# ATMega16Motherboard1.net
KiCad netlist of a schematic drawn in EAGLE
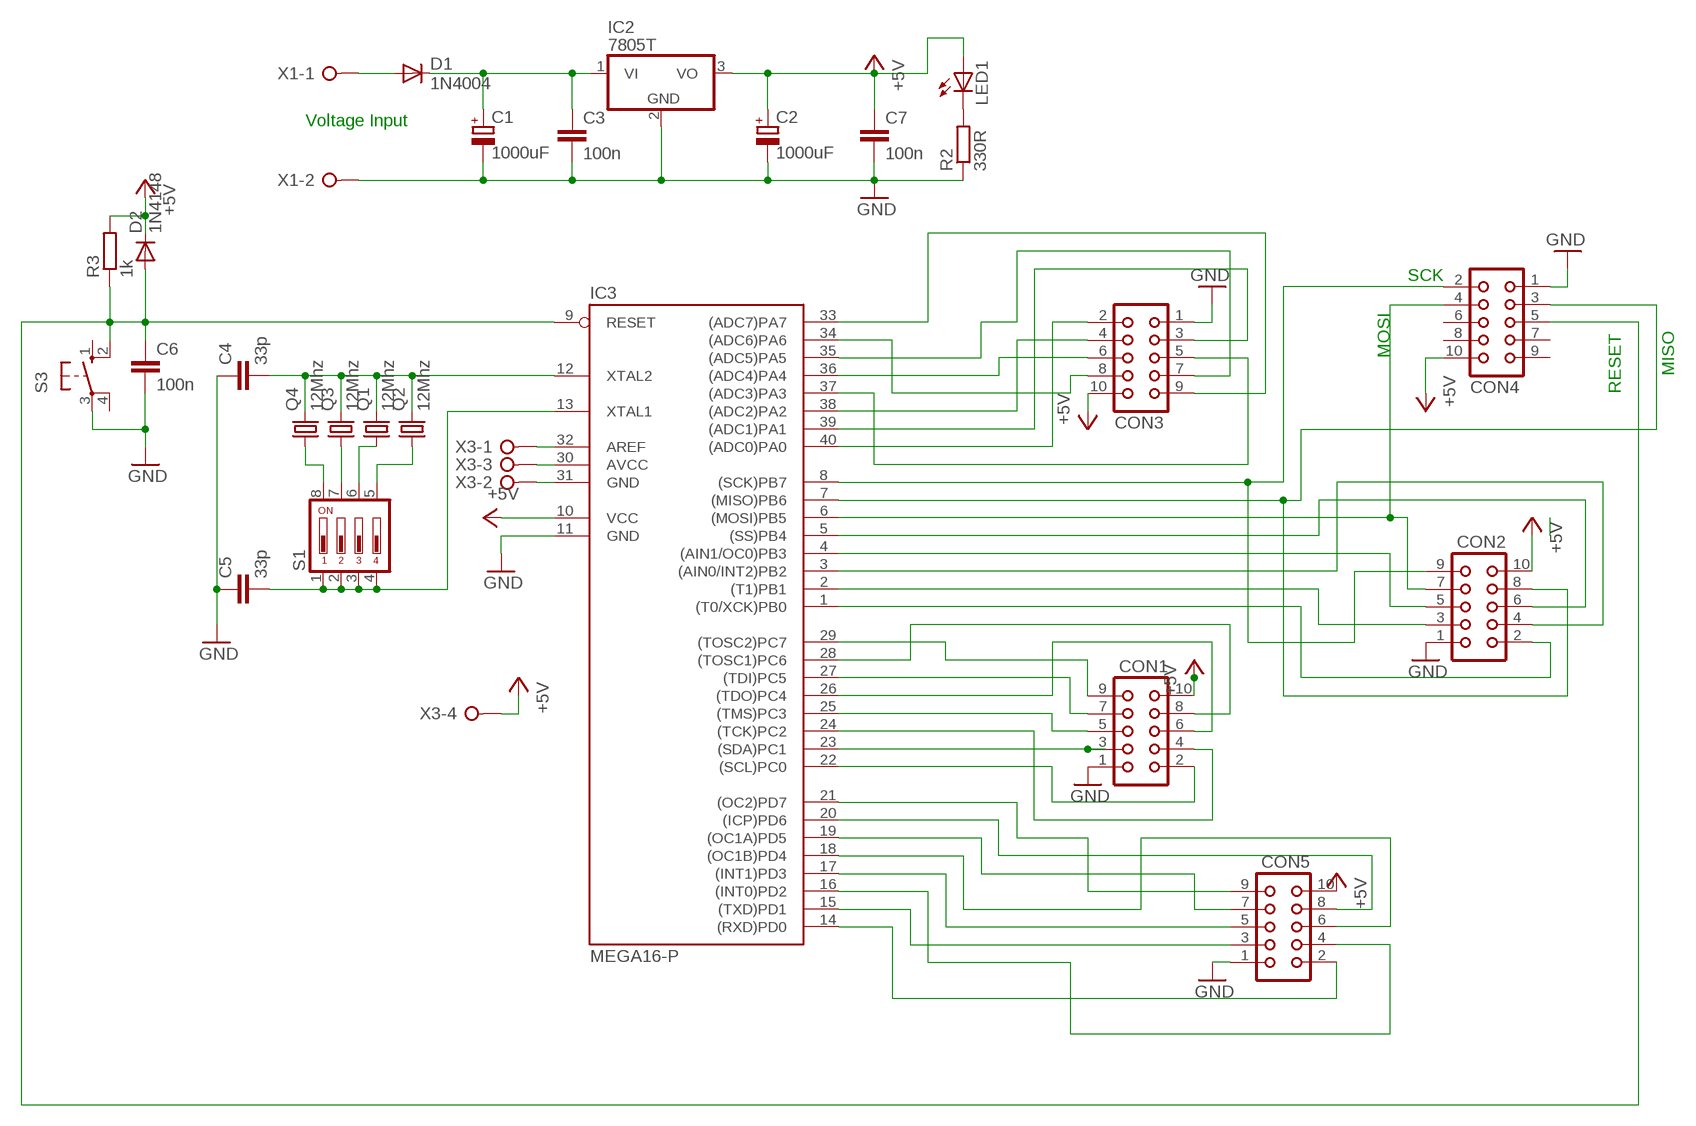
[diagram p0: schematic, sheet 1]

(export (version "E")
  (design (tool "Eeschema 10.0.6"))
  (components
    (comp (ref "C1")
      (value "1000uF")
      (footprint "eagle-import:E2,5-7")
      (libsource (lib "eagle-import") (part "CPOL-EUE2.5-7"))
    )
    (comp (ref "C2")
      (value "1000uF")
      (footprint "eagle-import:E2,5-7")
      (libsource (lib "eagle-import") (part "CPOL-EUE2.5-7"))
    )
    (comp (ref "C3")
      (value "100n")
      (footprint "eagle-import:C025-024X044")
      (libsource (lib "eagle-import") (part "C-EU025-024X044"))
    )
    (comp (ref "C4")
      (value "33p")
      (footprint "eagle-import:C025-024X044")
      (libsource (lib "eagle-import") (part "C-EU025-024X044"))
    )
    (comp (ref "C5")
      (value "33p")
      (footprint "eagle-import:C025-024X044")
      (libsource (lib "eagle-import") (part "C-EU025-024X044"))
    )
    (comp (ref "C6")
      (value "100n")
      (footprint "eagle-import:C025-024X044")
      (libsource (lib "eagle-import") (part "C-EU025-024X044"))
    )
    (comp (ref "C7")
      (value "100n")
      (footprint "eagle-import:C025-024X044")
      (libsource (lib "eagle-import") (part "C-EU025-024X044"))
    )
    (comp (ref "CON1")
      (value "CON10")
      (footprint "eagle-import:CON10")
      (libsource (lib "eagle-import") (part "CON10"))
    )
    (comp (ref "CON2")
      (value "CON10")
      (footprint "eagle-import:CON10")
      (libsource (lib "eagle-import") (part "CON10"))
    )
    (comp (ref "CON3")
      (value "CON10")
      (footprint "eagle-import:CON10")
      (libsource (lib "eagle-import") (part "CON10"))
    )
    (comp (ref "CON4")
      (value "CON10")
      (footprint "eagle-import:CON10")
      (libsource (lib "eagle-import") (part "CON10"))
    )
    (comp (ref "CON5")
      (value "CON10")
      (footprint "eagle-import:CON10")
      (libsource (lib "eagle-import") (part "CON10"))
    )
    (comp (ref "D1")
      (value "1N4004")
      (footprint "eagle-import:DO41-10")
      (libsource (lib "eagle-import") (part "1N4004"))
    )
    (comp (ref "D2")
      (value "1N4148")
      (footprint "eagle-import:DO35-10")
      (libsource (lib "eagle-import") (part "1N4148"))
    )
    (comp (ref "IC2")
      (value "7805T")
      (footprint "eagle-import:TO220H")
      (libsource (lib "eagle-import") (part "78T05"))
    )
    (comp (ref "IC3")
      (value "MEGA16-P")
      (footprint "eagle-import:DIL40")
      (fields (field (name "MPN") "ATMEGA16-16PU"))
      (libsource (lib "eagle-import") (part "MEGA16-P"))
    )
    (comp (ref "LED1")
      (value "LED5MM")
      (footprint "eagle-import:LED5MM")
      (libsource (lib "eagle-import") (part "LED5MM"))
    )
    (comp (ref "Q1")
      (value "12Mhz")
      (footprint "eagle-import:HC18U-V")
      (libsource (lib "eagle-import") (part "CRYSTALHC18U-V"))
    )
    (comp (ref "Q2")
      (value "12Mhz")
      (footprint "eagle-import:HC18U-V")
      (libsource (lib "eagle-import") (part "CRYSTALHC18U-V"))
    )
    (comp (ref "Q3")
      (value "12Mhz")
      (footprint "eagle-import:HC18U-V")
      (libsource (lib "eagle-import") (part "CRYSTALHC18U-V"))
    )
    (comp (ref "Q4")
      (value "12Mhz")
      (footprint "eagle-import:HC18U-V")
      (libsource (lib "eagle-import") (part "CRYSTALHC18U-V"))
    )
    (comp (ref "R2")
      (value "330R")
      (footprint "eagle-import:0204_5")
      (libsource (lib "eagle-import") (part "R-EU_0204/5"))
    )
    (comp (ref "R3")
      (value "1k")
      (footprint "eagle-import:0204_5")
      (libsource (lib "eagle-import") (part "R-EU_0204/5"))
    )
    (comp (ref "S1")
      (value "DIP04YL")
      (footprint "eagle-import:DIP04YL")
      (libsource (lib "eagle-import") (part "DIP04YL"))
    )
    (comp (ref "S3")
      (value "10-XX")
      (footprint "eagle-import:B3F-10XX")
      (fields (field (name "MPN") "B3F-1000"))
      (libsource (lib "eagle-import") (part "10-XX"))
    )
    (comp (ref "X1")
      (value "W237-02P")
      (footprint "eagle-import:W237-132")
      (libsource (lib "eagle-import") (part "W237-02P"))
    )
    (comp (ref "X3")
      (value "W237-04P")
      (footprint "eagle-import:W237-4P")
      (libsource (lib "eagle-import") (part "W237-04P"))
    )
  )
  (nets
    (net (code "1") (name "+5V") (class "Default")
      (node (ref "C2") (pin "+") (pinfunction "+_+") (pintype "passive"))
      (node (ref "C7") (pin "1") (pinfunction "1_1") (pintype "passive"))
      (node (ref "CON1") (pin "10") (pinfunction "10_10") (pintype "passive"))
      (node (ref "CON2") (pin "10") (pinfunction "10_10") (pintype "passive"))
      (node (ref "CON3") (pin "10") (pinfunction "10_10") (pintype "passive"))
      (node (ref "CON4") (pin "10") (pinfunction "10_10") (pintype "passive"))
      (node (ref "CON5") (pin "10") (pinfunction "10_10") (pintype "passive"))
      (node (ref "D2") (pin "C") (pinfunction "C_C") (pintype "passive"))
      (node (ref "IC2") (pin "3") (pinfunction "VO_3") (pintype "passive"))
      (node (ref "IC3") (pin "10") (pinfunction "VCC_10") (pintype "power_in"))
      (node (ref "LED1") (pin "A") (pinfunction "A_A") (pintype "passive"))
      (node (ref "R3") (pin "2") (pinfunction "2_2") (pintype "passive"))
      (node (ref "X3") (pin "4") (pinfunction "KL_4") (pintype "passive"))
    )
    (net (code "2") (name "GND") (class "Default")
      (node (ref "C1") (pin "-") (pinfunction "-_-") (pintype "passive"))
      (node (ref "C2") (pin "-") (pinfunction "-_-") (pintype "passive"))
      (node (ref "C3") (pin "2") (pinfunction "2_2") (pintype "passive"))
      (node (ref "C4") (pin "1") (pinfunction "1_1") (pintype "passive"))
      (node (ref "C5") (pin "1") (pinfunction "1_1") (pintype "passive"))
      (node (ref "C6") (pin "2") (pinfunction "2_2") (pintype "passive"))
      (node (ref "C7") (pin "2") (pinfunction "2_2") (pintype "passive"))
      (node (ref "CON1") (pin "1") (pinfunction "1_1") (pintype "passive"))
      (node (ref "CON2") (pin "1") (pinfunction "1_1") (pintype "passive"))
      (node (ref "CON3") (pin "1") (pinfunction "1_1") (pintype "passive"))
      (node (ref "CON4") (pin "1") (pinfunction "1_1") (pintype "passive"))
      (node (ref "CON5") (pin "1") (pinfunction "1_1") (pintype "passive"))
      (node (ref "IC2") (pin "2") (pinfunction "GND_2") (pintype "passive"))
      (node (ref "IC3") (pin "11") (pinfunction "GND_11") (pintype "power_in"))
      (node (ref "R2") (pin "1") (pinfunction "1_1") (pintype "passive"))
      (node (ref "S3") (pin "3") (pinfunction "P_3") (pintype "passive"))
      (node (ref "X1") (pin "2") (pinfunction "KL_2") (pintype "passive"))
    )
    (net (code "3") (name "Net-(IC2-VI)") (class "Default")
      (node (ref "C1") (pin "+") (pinfunction "+_+") (pintype "passive"))
      (node (ref "C3") (pin "1") (pinfunction "1_1") (pintype "passive"))
      (node (ref "D1") (pin "C") (pinfunction "C_C") (pintype "passive"))
      (node (ref "IC2") (pin "1") (pinfunction "VI_1") (pintype "input"))
    )
    (net (code "4") (name "Net-(IC3-(ADC0)PA0)") (class "Default")
      (node (ref "CON3") (pin "2") (pinfunction "2_2") (pintype "passive"))
      (node (ref "IC3") (pin "40") (pinfunction "(ADC0)PA0_40") (pintype "bidirectional"))
    )
    (net (code "5") (name "Net-(IC3-(ADC1)PA1)") (class "Default")
      (node (ref "CON3") (pin "3") (pinfunction "3_3") (pintype "passive"))
      (node (ref "IC3") (pin "39") (pinfunction "(ADC1)PA1_39") (pintype "bidirectional"))
    )
    (net (code "6") (name "Net-(IC3-(ADC2)PA2)") (class "Default")
      (node (ref "CON3") (pin "4") (pinfunction "4_4") (pintype "passive"))
      (node (ref "IC3") (pin "38") (pinfunction "(ADC2)PA2_38") (pintype "bidirectional"))
    )
    (net (code "7") (name "Net-(IC3-(ADC3)PA3)") (class "Default")
      (node (ref "CON3") (pin "5") (pinfunction "5_5") (pintype "passive"))
      (node (ref "IC3") (pin "37") (pinfunction "(ADC3)PA3_37") (pintype "bidirectional"))
    )
    (net (code "8") (name "Net-(IC3-(ADC4)PA4)") (class "Default")
      (node (ref "CON3") (pin "6") (pinfunction "6_6") (pintype "passive"))
      (node (ref "IC3") (pin "36") (pinfunction "(ADC4)PA4_36") (pintype "bidirectional"))
    )
    (net (code "9") (name "Net-(IC3-(ADC5)PA5)") (class "Default")
      (node (ref "CON3") (pin "7") (pinfunction "7_7") (pintype "passive"))
      (node (ref "IC3") (pin "35") (pinfunction "(ADC5)PA5_35") (pintype "bidirectional"))
    )
    (net (code "10") (name "Net-(IC3-(ADC6)PA6)") (class "Default")
      (node (ref "CON3") (pin "8") (pinfunction "8_8") (pintype "passive"))
      (node (ref "IC3") (pin "34") (pinfunction "(ADC6)PA6_34") (pintype "bidirectional"))
    )
    (net (code "11") (name "Net-(IC3-(ADC7)PA7)") (class "Default")
      (node (ref "CON3") (pin "9") (pinfunction "9_9") (pintype "passive"))
      (node (ref "IC3") (pin "33") (pinfunction "(ADC7)PA7_33") (pintype "bidirectional"))
    )
    (net (code "12") (name "Net-(IC3-(AIN0{slash}INT2)PB2)") (class "Default")
      (node (ref "CON2") (pin "4") (pinfunction "4_4") (pintype "passive"))
      (node (ref "IC3") (pin "3") (pinfunction "(AIN0/INT2)PB2_3") (pintype "bidirectional"))
    )
    (net (code "13") (name "Net-(IC3-(AIN1{slash}OC0)PB3)") (class "Default")
      (node (ref "CON2") (pin "5") (pinfunction "5_5") (pintype "passive"))
      (node (ref "IC3") (pin "4") (pinfunction "(AIN1/OC0)PB3_4") (pintype "bidirectional"))
    )
    (net (code "14") (name "Net-(IC3-(ICP)PD6)") (class "Default")
      (node (ref "CON5") (pin "8") (pinfunction "8_8") (pintype "passive"))
      (node (ref "IC3") (pin "20") (pinfunction "(ICP)PD6_20") (pintype "bidirectional"))
    )
    (net (code "15") (name "Net-(IC3-(INT0)PD2)") (class "Default")
      (node (ref "CON5") (pin "4") (pinfunction "4_4") (pintype "passive"))
      (node (ref "IC3") (pin "16") (pinfunction "(INT0)PD2_16") (pintype "bidirectional"))
    )
    (net (code "16") (name "Net-(IC3-(INT1)PD3)") (class "Default")
      (node (ref "CON5") (pin "5") (pinfunction "5_5") (pintype "passive"))
      (node (ref "IC3") (pin "17") (pinfunction "(INT1)PD3_17") (pintype "bidirectional"))
    )
    (net (code "17") (name "Net-(IC3-(MISO)PB6)") (class "Default")
      (node (ref "CON2") (pin "8") (pinfunction "8_8") (pintype "passive"))
      (node (ref "CON4") (pin "3") (pinfunction "3_3") (pintype "passive"))
      (node (ref "IC3") (pin "7") (pinfunction "(MISO)PB6_7") (pintype "bidirectional"))
    )
    (net (code "18") (name "Net-(IC3-(MOSI)PB5)") (class "Default")
      (node (ref "CON2") (pin "7") (pinfunction "7_7") (pintype "passive"))
      (node (ref "CON4") (pin "4") (pinfunction "4_4") (pintype "passive"))
      (node (ref "IC3") (pin "6") (pinfunction "(MOSI)PB5_6") (pintype "bidirectional"))
    )
    (net (code "19") (name "Net-(IC3-(OC1A)PD5)") (class "Default")
      (node (ref "CON5") (pin "7") (pinfunction "7_7") (pintype "passive"))
      (node (ref "IC3") (pin "19") (pinfunction "(OC1A)PD5_19") (pintype "bidirectional"))
    )
    (net (code "20") (name "Net-(IC3-(OC1B)PD4)") (class "Default")
      (node (ref "CON5") (pin "6") (pinfunction "6_6") (pintype "passive"))
      (node (ref "IC3") (pin "18") (pinfunction "(OC1B)PD4_18") (pintype "bidirectional"))
    )
    (net (code "21") (name "Net-(IC3-(OC2)PD7)") (class "Default")
      (node (ref "CON5") (pin "9") (pinfunction "9_9") (pintype "passive"))
      (node (ref "IC3") (pin "21") (pinfunction "(OC2)PD7_21") (pintype "bidirectional"))
    )
    (net (code "22") (name "Net-(IC3-(RXD)PD0)") (class "Default")
      (node (ref "CON5") (pin "2") (pinfunction "2_2") (pintype "passive"))
      (node (ref "IC3") (pin "14") (pinfunction "(RXD)PD0_14") (pintype "bidirectional"))
    )
    (net (code "23") (name "Net-(IC3-(SCK)PB7)") (class "Default")
      (node (ref "CON2") (pin "9") (pinfunction "9_9") (pintype "passive"))
      (node (ref "CON4") (pin "2") (pinfunction "2_2") (pintype "passive"))
      (node (ref "IC3") (pin "8") (pinfunction "(SCK)PB7_8") (pintype "bidirectional"))
    )
    (net (code "24") (name "Net-(IC3-(SCL)PC0)") (class "Default")
      (node (ref "CON1") (pin "2") (pinfunction "2_2") (pintype "passive"))
      (node (ref "IC3") (pin "22") (pinfunction "(SCL)PC0_22") (pintype "bidirectional"))
    )
    (net (code "25") (name "Net-(IC3-(SDA)PC1)") (class "Default")
      (node (ref "CON1") (pin "3") (pinfunction "3_3") (pintype "passive"))
      (node (ref "IC3") (pin "23") (pinfunction "(SDA)PC1_23") (pintype "bidirectional"))
    )
    (net (code "26") (name "Net-(IC3-(SS)PB4)") (class "Default")
      (node (ref "CON2") (pin "6") (pinfunction "6_6") (pintype "passive"))
      (node (ref "IC3") (pin "5") (pinfunction "(SS)PB4_5") (pintype "bidirectional"))
    )
    (net (code "27") (name "Net-(IC3-(T0{slash}XCK)PB0)") (class "Default")
      (node (ref "CON2") (pin "2") (pinfunction "2_2") (pintype "passive"))
      (node (ref "IC3") (pin "1") (pinfunction "(T0/XCK)PB0_1") (pintype "bidirectional"))
    )
    (net (code "28") (name "Net-(IC3-(T1)PB1)") (class "Default")
      (node (ref "CON2") (pin "3") (pinfunction "3_3") (pintype "passive"))
      (node (ref "IC3") (pin "2") (pinfunction "(T1)PB1_2") (pintype "bidirectional"))
    )
    (net (code "29") (name "Net-(IC3-(TCK)PC2)") (class "Default")
      (node (ref "CON1") (pin "4") (pinfunction "4_4") (pintype "passive"))
      (node (ref "IC3") (pin "24") (pinfunction "(TCK)PC2_24") (pintype "bidirectional"))
    )
    (net (code "30") (name "Net-(IC3-(TDI)PC5)") (class "Default")
      (node (ref "CON1") (pin "7") (pinfunction "7_7") (pintype "passive"))
      (node (ref "IC3") (pin "27") (pinfunction "(TDI)PC5_27") (pintype "bidirectional"))
    )
    (net (code "31") (name "Net-(IC3-(TDO)PC4)") (class "Default")
      (node (ref "CON1") (pin "6") (pinfunction "6_6") (pintype "passive"))
      (node (ref "IC3") (pin "26") (pinfunction "(TDO)PC4_26") (pintype "bidirectional"))
    )
    (net (code "32") (name "Net-(IC3-(TMS)PC3)") (class "Default")
      (node (ref "CON1") (pin "5") (pinfunction "5_5") (pintype "passive"))
      (node (ref "IC3") (pin "25") (pinfunction "(TMS)PC3_25") (pintype "bidirectional"))
    )
    (net (code "33") (name "Net-(IC3-(TOSC1)PC6)") (class "Default")
      (node (ref "CON1") (pin "8") (pinfunction "8_8") (pintype "passive"))
      (node (ref "IC3") (pin "28") (pinfunction "(TOSC1)PC6_28") (pintype "bidirectional"))
    )
    (net (code "34") (name "Net-(IC3-(TOSC2)PC7)") (class "Default")
      (node (ref "CON1") (pin "9") (pinfunction "9_9") (pintype "passive"))
      (node (ref "IC3") (pin "29") (pinfunction "(TOSC2)PC7_29") (pintype "bidirectional"))
    )
    (net (code "35") (name "Net-(IC3-(TXD)PD1)") (class "Default")
      (node (ref "CON5") (pin "3") (pinfunction "3_3") (pintype "passive"))
      (node (ref "IC3") (pin "15") (pinfunction "(TXD)PD1_15") (pintype "bidirectional"))
    )
    (net (code "36") (name "Net-(IC3-AREF)") (class "Default")
      (node (ref "IC3") (pin "32") (pinfunction "AREF_32") (pintype "passive"))
      (node (ref "X3") (pin "1") (pinfunction "KL_1") (pintype "passive"))
    )
    (net (code "37") (name "Net-(IC3-AVCC)") (class "Default")
      (node (ref "IC3") (pin "30") (pinfunction "AVCC_30") (pintype "power_in"))
      (node (ref "X3") (pin "3") (pinfunction "KL_3") (pintype "passive"))
    )
    (net (code "38") (name "Net-(IC3-RESET)") (class "Default")
      (node (ref "C6") (pin "1") (pinfunction "1_1") (pintype "passive"))
      (node (ref "CON4") (pin "5") (pinfunction "5_5") (pintype "passive"))
      (node (ref "D2") (pin "A") (pinfunction "A_A") (pintype "passive"))
      (node (ref "IC3") (pin "9") (pinfunction "RESET_9") (pintype "input"))
      (node (ref "R3") (pin "1") (pinfunction "1_1") (pintype "passive"))
      (node (ref "S3") (pin "2") (pinfunction "S1_2") (pintype "passive"))
    )
    (net (code "39") (name "Net-(IC3-XTAL1)") (class "Default")
      (node (ref "C5") (pin "2") (pinfunction "2_2") (pintype "passive"))
      (node (ref "IC3") (pin "13") (pinfunction "XTAL1_13") (pintype "bidirectional"))
      (node (ref "S1") (pin "1") (pinfunction "1_1") (pintype "passive"))
      (node (ref "S1") (pin "2") (pinfunction "2_2") (pintype "passive"))
      (node (ref "S1") (pin "3") (pinfunction "3_3") (pintype "passive"))
      (node (ref "S1") (pin "4") (pinfunction "4_4") (pintype "passive"))
    )
    (net (code "40") (name "Net-(IC3-XTAL2)") (class "Default")
      (node (ref "C4") (pin "2") (pinfunction "2_2") (pintype "passive"))
      (node (ref "IC3") (pin "12") (pinfunction "XTAL2_12") (pintype "bidirectional"))
      (node (ref "Q1") (pin "2") (pinfunction "2_2") (pintype "passive"))
      (node (ref "Q2") (pin "2") (pinfunction "2_2") (pintype "passive"))
      (node (ref "Q3") (pin "2") (pinfunction "2_2") (pintype "passive"))
      (node (ref "Q4") (pin "2") (pinfunction "2_2") (pintype "passive"))
    )
    (net (code "41") (name "Net-(LED1-C)") (class "Default")
      (node (ref "LED1") (pin "K") (pinfunction "C_K") (pintype "passive"))
      (node (ref "R2") (pin "2") (pinfunction "2_2") (pintype "passive"))
    )
    (net (code "42") (name "Net-(Q1-Pad1)") (class "Default")
      (node (ref "Q1") (pin "1") (pinfunction "1_1") (pintype "passive"))
      (node (ref "S1") (pin "6") (pinfunction "6_6") (pintype "passive"))
    )
    (net (code "43") (name "Net-(Q2-Pad1)") (class "Default")
      (node (ref "Q2") (pin "1") (pinfunction "1_1") (pintype "passive"))
      (node (ref "S1") (pin "5") (pinfunction "5_5") (pintype "passive"))
    )
    (net (code "44") (name "Net-(Q3-Pad1)") (class "Default")
      (node (ref "Q3") (pin "1") (pinfunction "1_1") (pintype "passive"))
      (node (ref "S1") (pin "7") (pinfunction "7_7") (pintype "passive"))
    )
    (net (code "45") (name "Net-(Q4-Pad1)") (class "Default")
      (node (ref "Q4") (pin "1") (pinfunction "1_1") (pintype "passive"))
      (node (ref "S1") (pin "8") (pinfunction "8_8") (pintype "passive"))
    )
    (net (code "46") (name "Net-(X1A-KL)") (class "Default")
      (node (ref "D1") (pin "A") (pinfunction "A_A") (pintype "passive"))
      (node (ref "X1") (pin "1") (pinfunction "KL_1") (pintype "passive"))
    )
    (net (code "47") (name "Net-(X3B-KL)") (class "Default")
      (node (ref "IC3") (pin "31") (pinfunction "GND_31") (pintype "power_in"))
      (node (ref "X3") (pin "2") (pinfunction "KL_2") (pintype "passive"))
    )
    (net (code "48") (name "unconnected-(CON4-Pad6)") (class "Default")
      (node (ref "CON4") (pin "6") (pinfunction "6_6") (pintype "passive"))
    )
    (net (code "49") (name "unconnected-(CON4-Pad7)") (class "Default")
      (node (ref "CON4") (pin "7") (pinfunction "7_7") (pintype "passive"))
    )
    (net (code "50") (name "unconnected-(CON4-Pad8)") (class "Default")
      (node (ref "CON4") (pin "8") (pinfunction "8_8") (pintype "passive"))
    )
    (net (code "51") (name "unconnected-(CON4-Pad9)") (class "Default")
      (node (ref "CON4") (pin "9") (pinfunction "9_9") (pintype "passive"))
    )
    (net (code "52") (name "unconnected-(S3-P1-Pad4)") (class "Default")
      (node (ref "S3") (pin "4") (pinfunction "P1_4") (pintype "passive"))
    )
    (net (code "53") (name "unconnected-(S3-S-Pad1)") (class "Default")
      (node (ref "S3") (pin "1") (pinfunction "S_1") (pintype "passive"))
    )
  )
)
